# PreAmplifier_ToneController.net
KiCad netlist of a schematic drawn in Altium Designer
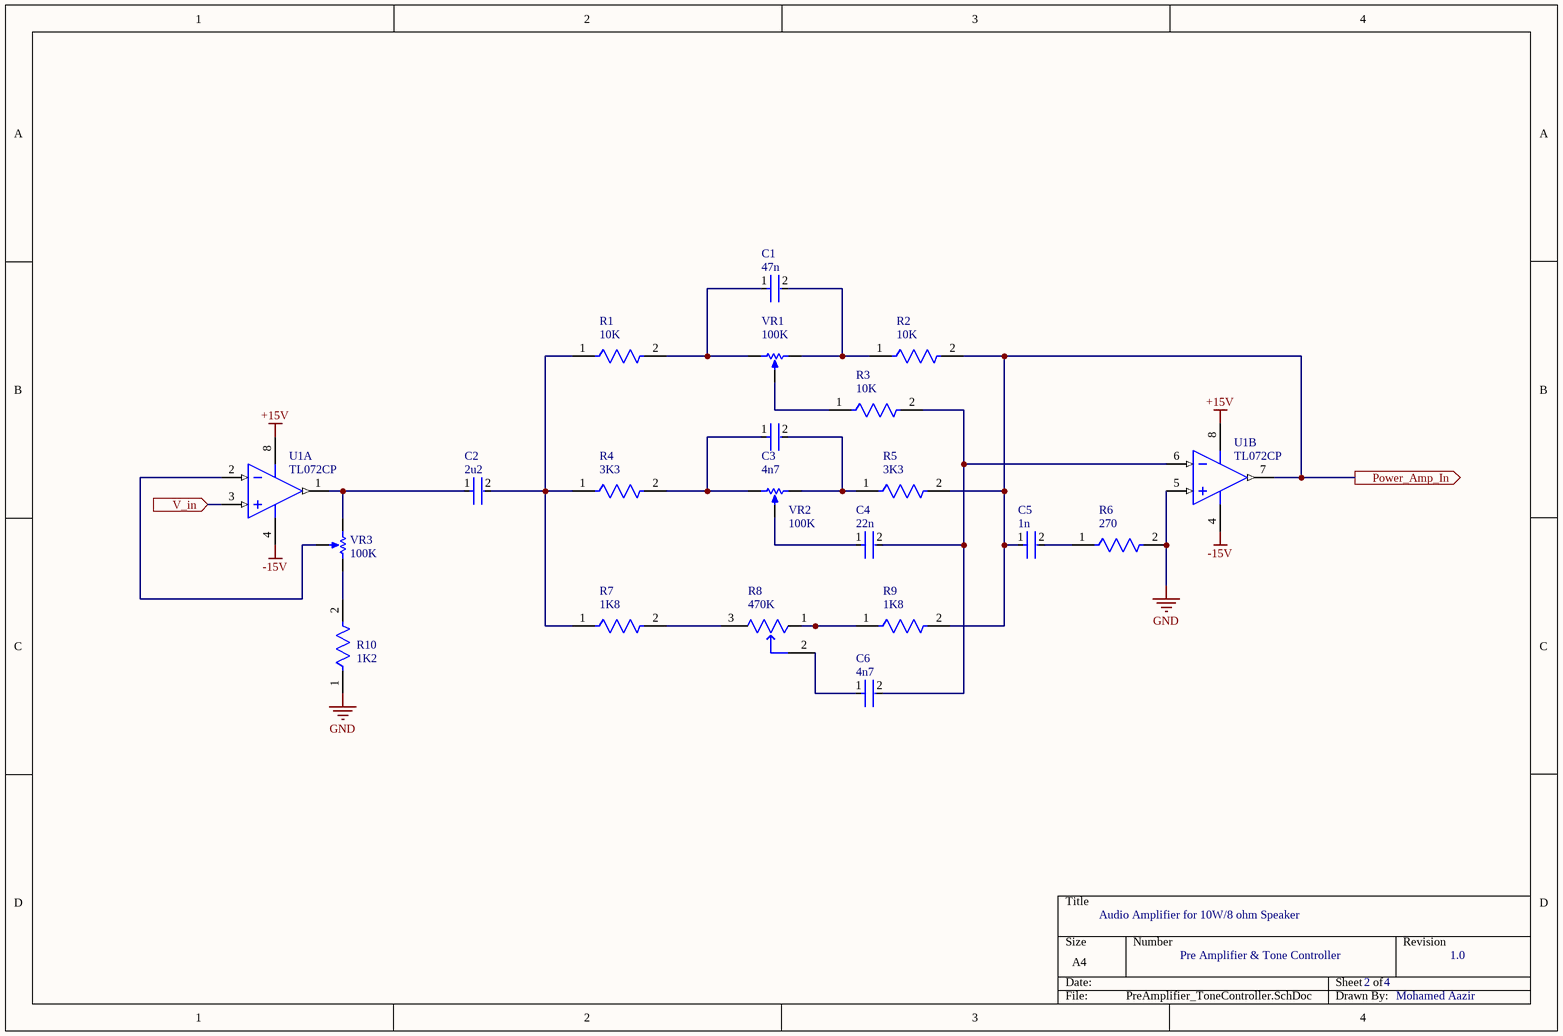
[diagram p0: PreAmplifier_ToneController.SchDoc]

(export (version "E")
  (design (tool "Eeschema 10.0.6"))
  (components
    (comp (ref "C1")
      (value "47n")
      (footprint "FP-RAD-TH-D_5_0_5-L_11_1-MFG")
      (description "Aluminum Electrolytic Capacitors (Radial Lead Type) 22uF ±20% 25V")
      (fields (field (name "TOLERANCE") "20%") (field (name "VOLTAGE") "25V"))
      (libsource (lib "Altium Content Vault") (part "b4654b650e69147ec39a6b967a45e02"))
    )
    (comp (ref "C2")
      (value "2u2")
      (footprint "FP-RAD-TH-D_5_0_5-L_11_1-MFG")
      (description "Aluminum Electrolytic Capacitors (Radial Lead Type) 22uF ±20% 25V")
      (fields (field (name "TOLERANCE") "20%") (field (name "VOLTAGE") "25V"))
      (libsource (lib "Altium Content Vault") (part "b4654b650e69147ec39a6b967a45e02"))
    )
    (comp (ref "C3")
      (value "4n7")
      (footprint "FP-RAD-TH-D_5_0_5-L_11_1-MFG")
      (description "Aluminum Electrolytic Capacitors (Radial Lead Type) 22uF ±20% 25V")
      (fields (field (name "TOLERANCE") "20%") (field (name "VOLTAGE") "25V"))
      (libsource (lib "Altium Content Vault") (part "b4654b650e69147ec39a6b967a45e02"))
    )
    (comp (ref "C4")
      (value "22n")
      (footprint "FP-RAD-TH-D_5_0_5-L_11_1-MFG")
      (description "Aluminum Electrolytic Capacitors (Radial Lead Type) 22uF ±20% 25V")
      (fields (field (name "TOLERANCE") "20%") (field (name "VOLTAGE") "25V"))
      (libsource (lib "Altium Content Vault") (part "b4654b650e69147ec39a6b967a45e02"))
    )
    (comp (ref "C5")
      (value "1n")
      (footprint "FP-RAD-TH-D_5_0_5-L_11_1-MFG")
      (description "Aluminum Electrolytic Capacitors (Radial Lead Type) 22uF ±20% 25V")
      (fields (field (name "TOLERANCE") "20%") (field (name "VOLTAGE") "25V"))
      (libsource (lib "Altium Content Vault") (part "b4654b650e69147ec39a6b967a45e02"))
    )
    (comp (ref "C6")
      (value "4n7")
      (footprint "FP-RAD-TH-D_5_0_5-L_11_1-MFG")
      (description "Aluminum Electrolytic Capacitors (Radial Lead Type) 22uF ±20% 25V")
      (fields (field (name "TOLERANCE") "20%") (field (name "VOLTAGE") "25V"))
      (libsource (lib "Altium Content Vault") (part "b4654b650e69147ec39a6b967a45e02"))
    )
    (comp (ref "R1")
      (value "10K")
      (footprint "FP-MFR-25-MFG")
      (description "RES 1.18K OHM 1/4W 1% AXIAL")
      (fields (field (name "MANUFACTURER") "Yageo") (field (name "TOLERANCE") "1%"))
      (libsource (lib "Altium Content Vault") (part "1029c3af85768c4190bb7ad29bc67b5"))
    )
    (comp (ref "R2")
      (value "10K")
      (footprint "FP-MFR-25-MFG")
      (description "RES 1.18K OHM 1/4W 1% AXIAL")
      (fields (field (name "MANUFACTURER") "Yageo") (field (name "TOLERANCE") "1%"))
      (libsource (lib "Altium Content Vault") (part "1029c3af85768c4190bb7ad29bc67b5"))
    )
    (comp (ref "R3")
      (value "10K")
      (footprint "FP-MFR-25-MFG")
      (description "RES 1.18K OHM 1/4W 1% AXIAL")
      (fields (field (name "MANUFACTURER") "Yageo") (field (name "TOLERANCE") "1%"))
      (libsource (lib "Altium Content Vault") (part "1029c3af85768c4190bb7ad29bc67b5"))
    )
    (comp (ref "R4")
      (value "3K3")
      (footprint "FP-MFR-25-MFG")
      (description "RES 1.18K OHM 1/4W 1% AXIAL")
      (fields (field (name "MANUFACTURER") "Yageo") (field (name "TOLERANCE") "1%"))
      (libsource (lib "Altium Content Vault") (part "1029c3af85768c4190bb7ad29bc67b5"))
    )
    (comp (ref "R5")
      (value "3K3")
      (footprint "FP-MFR-25-MFG")
      (description "RES 1.18K OHM 1/4W 1% AXIAL")
      (fields (field (name "MANUFACTURER") "Yageo") (field (name "TOLERANCE") "1%"))
      (libsource (lib "Altium Content Vault") (part "1029c3af85768c4190bb7ad29bc67b5"))
    )
    (comp (ref "R6")
      (value "270")
      (footprint "FP-MFR-25-MFG")
      (description "RES 1.18K OHM 1/4W 1% AXIAL")
      (fields (field (name "MANUFACTURER") "Yageo") (field (name "TOLERANCE") "1%"))
      (libsource (lib "Altium Content Vault") (part "1029c3af85768c4190bb7ad29bc67b5"))
    )
    (comp (ref "R7")
      (value "1K8")
      (footprint "FP-MFR-25-MFG")
      (description "RES 1.18K OHM 1/4W 1% AXIAL")
      (fields (field (name "MANUFACTURER") "Yageo") (field (name "TOLERANCE") "1%"))
      (libsource (lib "Altium Content Vault") (part "1029c3af85768c4190bb7ad29bc67b5"))
    )
    (comp (ref "R8")
      (value "470K")
      (footprint "FP-PV37W-MFG")
      (description "TRIMMER 500KOHM 0.25W PC PIN TOP")
      (fields (field (name "TOLERANCE") "10%") (field (name "MANUFACTURER PART NUMBER") "PV37W504C01B00"))
      (libsource (lib "Altium Content Vault") (part "d5b3b410a8022890c459c25b800d772"))
    )
    (comp (ref "R9")
      (value "1K8")
      (footprint "FP-MFR-25-MFG")
      (description "RES 1.18K OHM 1/4W 1% AXIAL")
      (fields (field (name "MANUFACTURER") "Yageo") (field (name "TOLERANCE") "1%"))
      (libsource (lib "Altium Content Vault") (part "1029c3af85768c4190bb7ad29bc67b5"))
    )
    (comp (ref "R10")
      (value "1K2")
      (footprint "FP-MFR-25-MFG")
      (description "RES 1.18K OHM 1/4W 1% AXIAL")
      (fields (field (name "MANUFACTURER") "Yageo") (field (name "TOLERANCE") "1%"))
      (libsource (lib "Altium Content Vault") (part "1029c3af85768c4190bb7ad29bc67b5"))
    )
    (comp (ref "U1")
      (value "TL072CP")
      (footprint "P0008A")
      (fields (field (name "MANUFACTURER") "Texas Instruments"))
      (libsource (lib "Altium Content Vault") (part "TI-AMP-D6-2-8_D"))
    )
    (comp (ref "VR1")
      (value "100K")
      (footprint "BOUR-3362P")
      (description "Square Trimpot(R) Trimming Potentiometer, 100 KOhm, 300 V, -55 to 125 degC, 3-Pin THD, RoHS, Tube")
      (fields (field (name "TOLERANCE") "1%"))
      (libsource (lib "Altium Content Vault") (part "RES-POT-3"))
    )
    (comp (ref "VR2")
      (value "100K")
      (footprint "BOUR-3362P")
      (description "Square Trimpot(R) Trimming Potentiometer, 100 KOhm, 300 V, -55 to 125 degC, 3-Pin THD, RoHS, Tube")
      (fields (field (name "TOLERANCE") "1%"))
      (libsource (lib "Altium Content Vault") (part "RES-POT-3"))
    )
    (comp (ref "VR3")
      (value "100K")
      (footprint "BOUR-3362P")
      (description "Square Trimpot(R) Trimming Potentiometer, 100 KOhm, 300 V, -55 to 125 degC, 3-Pin THD, RoHS, Tube")
      (fields (field (name "TOLERANCE") "1%"))
      (libsource (lib "Altium Content Vault") (part "RES-POT-3"))
    )
  )
  (nets
    (net (code "1") (name "+15V") (class "Default")
      (node (ref "U1") (pin "8") (pinfunction "VCC+_8") (pintype "power_in"))
    )
    (net (code "2") (name "-15V") (class "Default")
      (node (ref "U1") (pin "4") (pinfunction "VCC-_4") (pintype "power_in"))
    )
    (net (code "3") (name "/Power_Amp_In") (class "Default")
      (node (ref "C5") (pin "1") (pinfunction "1_1") (pintype "passive"))
      (node (ref "R2") (pin "2") (pinfunction "2_2") (pintype "passive"))
      (node (ref "R5") (pin "2") (pinfunction "2_2") (pintype "passive"))
      (node (ref "R9") (pin "2") (pinfunction "2_2") (pintype "passive"))
      (node (ref "U1") (pin "7") (pinfunction "OUT2_7") (pintype "output"))
    )
    (net (code "4") (name "/V_in") (class "Default")
      (node (ref "U1") (pin "3") (pinfunction "IN1+_3") (pintype "input"))
    )
    (net (code "5") (name "GND") (class "Default")
      (node (ref "R10") (pin "1") (pinfunction "1_1") (pintype "passive"))
      (node (ref "R6") (pin "2") (pinfunction "2_2") (pintype "passive"))
      (node (ref "U1") (pin "5") (pinfunction "IN2+_5") (pintype "input"))
    )
    (net (code "6") (name "Net-(C2-Pad2)") (class "Default")
      (node (ref "C2") (pin "2") (pinfunction "2_2") (pintype "passive"))
      (node (ref "R1") (pin "1") (pinfunction "1_1") (pintype "passive"))
      (node (ref "R4") (pin "1") (pinfunction "1_1") (pintype "passive"))
      (node (ref "R7") (pin "1") (pinfunction "1_1") (pintype "passive"))
    )
    (net (code "7") (name "Net-(C5-Pad2)") (class "Default")
      (node (ref "C5") (pin "2") (pinfunction "2_2") (pintype "passive"))
      (node (ref "R6") (pin "1") (pinfunction "1_1") (pintype "passive"))
    )
    (net (code "8") (name "Net-(C6-Pad1)") (class "Default")
      (node (ref "C6") (pin "1") (pinfunction "1_1") (pintype "passive"))
      (node (ref "R8") (pin "2") (pinfunction "2_2") (pintype "passive"))
    )
    (net (code "9") (name "Net-(R7-Pad2)") (class "Default")
      (node (ref "R7") (pin "2") (pinfunction "2_2") (pintype "passive"))
      (node (ref "R8") (pin "3") (pinfunction "3_3") (pintype "passive"))
    )
    (net (code "10") (name "Net-(R8-Pad1)") (class "Default")
      (node (ref "R8") (pin "1") (pinfunction "1_1") (pintype "passive"))
      (node (ref "R9") (pin "1") (pinfunction "1_1") (pintype "passive"))
    )
    (net (code "11") (name "Net-(U1A-IN1-)") (class "Default")
      (node (ref "U1") (pin "2") (pinfunction "IN1-_2") (pintype "input"))
      (node (ref "VR3") (pin "2") (pinfunction "S_2") (pintype "passive"))
    )
    (net (code "12") (name "Net-(U1A-OUT1)") (class "Default")
      (node (ref "C2") (pin "1") (pinfunction "1_1") (pintype "passive"))
      (node (ref "U1") (pin "1") (pinfunction "OUT1_1") (pintype "output"))
      (node (ref "VR3") (pin "1") (pinfunction "CCW_1") (pintype "passive"))
    )
    (net (code "13") (name "Net-(U1B-IN2-)") (class "Default")
      (node (ref "C4") (pin "2") (pinfunction "2_2") (pintype "passive"))
      (node (ref "C6") (pin "2") (pinfunction "2_2") (pintype "passive"))
      (node (ref "R3") (pin "2") (pinfunction "2_2") (pintype "passive"))
      (node (ref "U1") (pin "6") (pinfunction "IN2-_6") (pintype "input"))
    )
    (net (code "14") (name "Net-(VR1-CCW)") (class "Default")
      (node (ref "C1") (pin "1") (pinfunction "1_1") (pintype "passive"))
      (node (ref "R1") (pin "2") (pinfunction "2_2") (pintype "passive"))
      (node (ref "VR1") (pin "1") (pinfunction "CCW_1") (pintype "passive"))
    )
    (net (code "15") (name "Net-(VR1-CW)") (class "Default")
      (node (ref "C1") (pin "2") (pinfunction "2_2") (pintype "passive"))
      (node (ref "R2") (pin "1") (pinfunction "1_1") (pintype "passive"))
      (node (ref "VR1") (pin "3") (pinfunction "CW_3") (pintype "passive"))
    )
    (net (code "16") (name "Net-(VR1-S)") (class "Default")
      (node (ref "R3") (pin "1") (pinfunction "1_1") (pintype "passive"))
      (node (ref "VR1") (pin "2") (pinfunction "S_2") (pintype "passive"))
    )
    (net (code "17") (name "Net-(VR2-CCW)") (class "Default")
      (node (ref "C3") (pin "1") (pinfunction "1_1") (pintype "passive"))
      (node (ref "R4") (pin "2") (pinfunction "2_2") (pintype "passive"))
      (node (ref "VR2") (pin "1") (pinfunction "CCW_1") (pintype "passive"))
    )
    (net (code "18") (name "Net-(VR2-CW)") (class "Default")
      (node (ref "C3") (pin "2") (pinfunction "2_2") (pintype "passive"))
      (node (ref "R5") (pin "1") (pinfunction "1_1") (pintype "passive"))
      (node (ref "VR2") (pin "3") (pinfunction "CW_3") (pintype "passive"))
    )
    (net (code "19") (name "Net-(VR2-S)") (class "Default")
      (node (ref "C4") (pin "1") (pinfunction "1_1") (pintype "passive"))
      (node (ref "VR2") (pin "2") (pinfunction "S_2") (pintype "passive"))
    )
    (net (code "20") (name "Net-(VR3-CW)") (class "Default")
      (node (ref "R10") (pin "2") (pinfunction "2_2") (pintype "passive"))
      (node (ref "VR3") (pin "3") (pinfunction "CW_3") (pintype "passive"))
    )
  )
)
